# Power_Management.net
KiCad netlist of a schematic drawn in Altium Designer
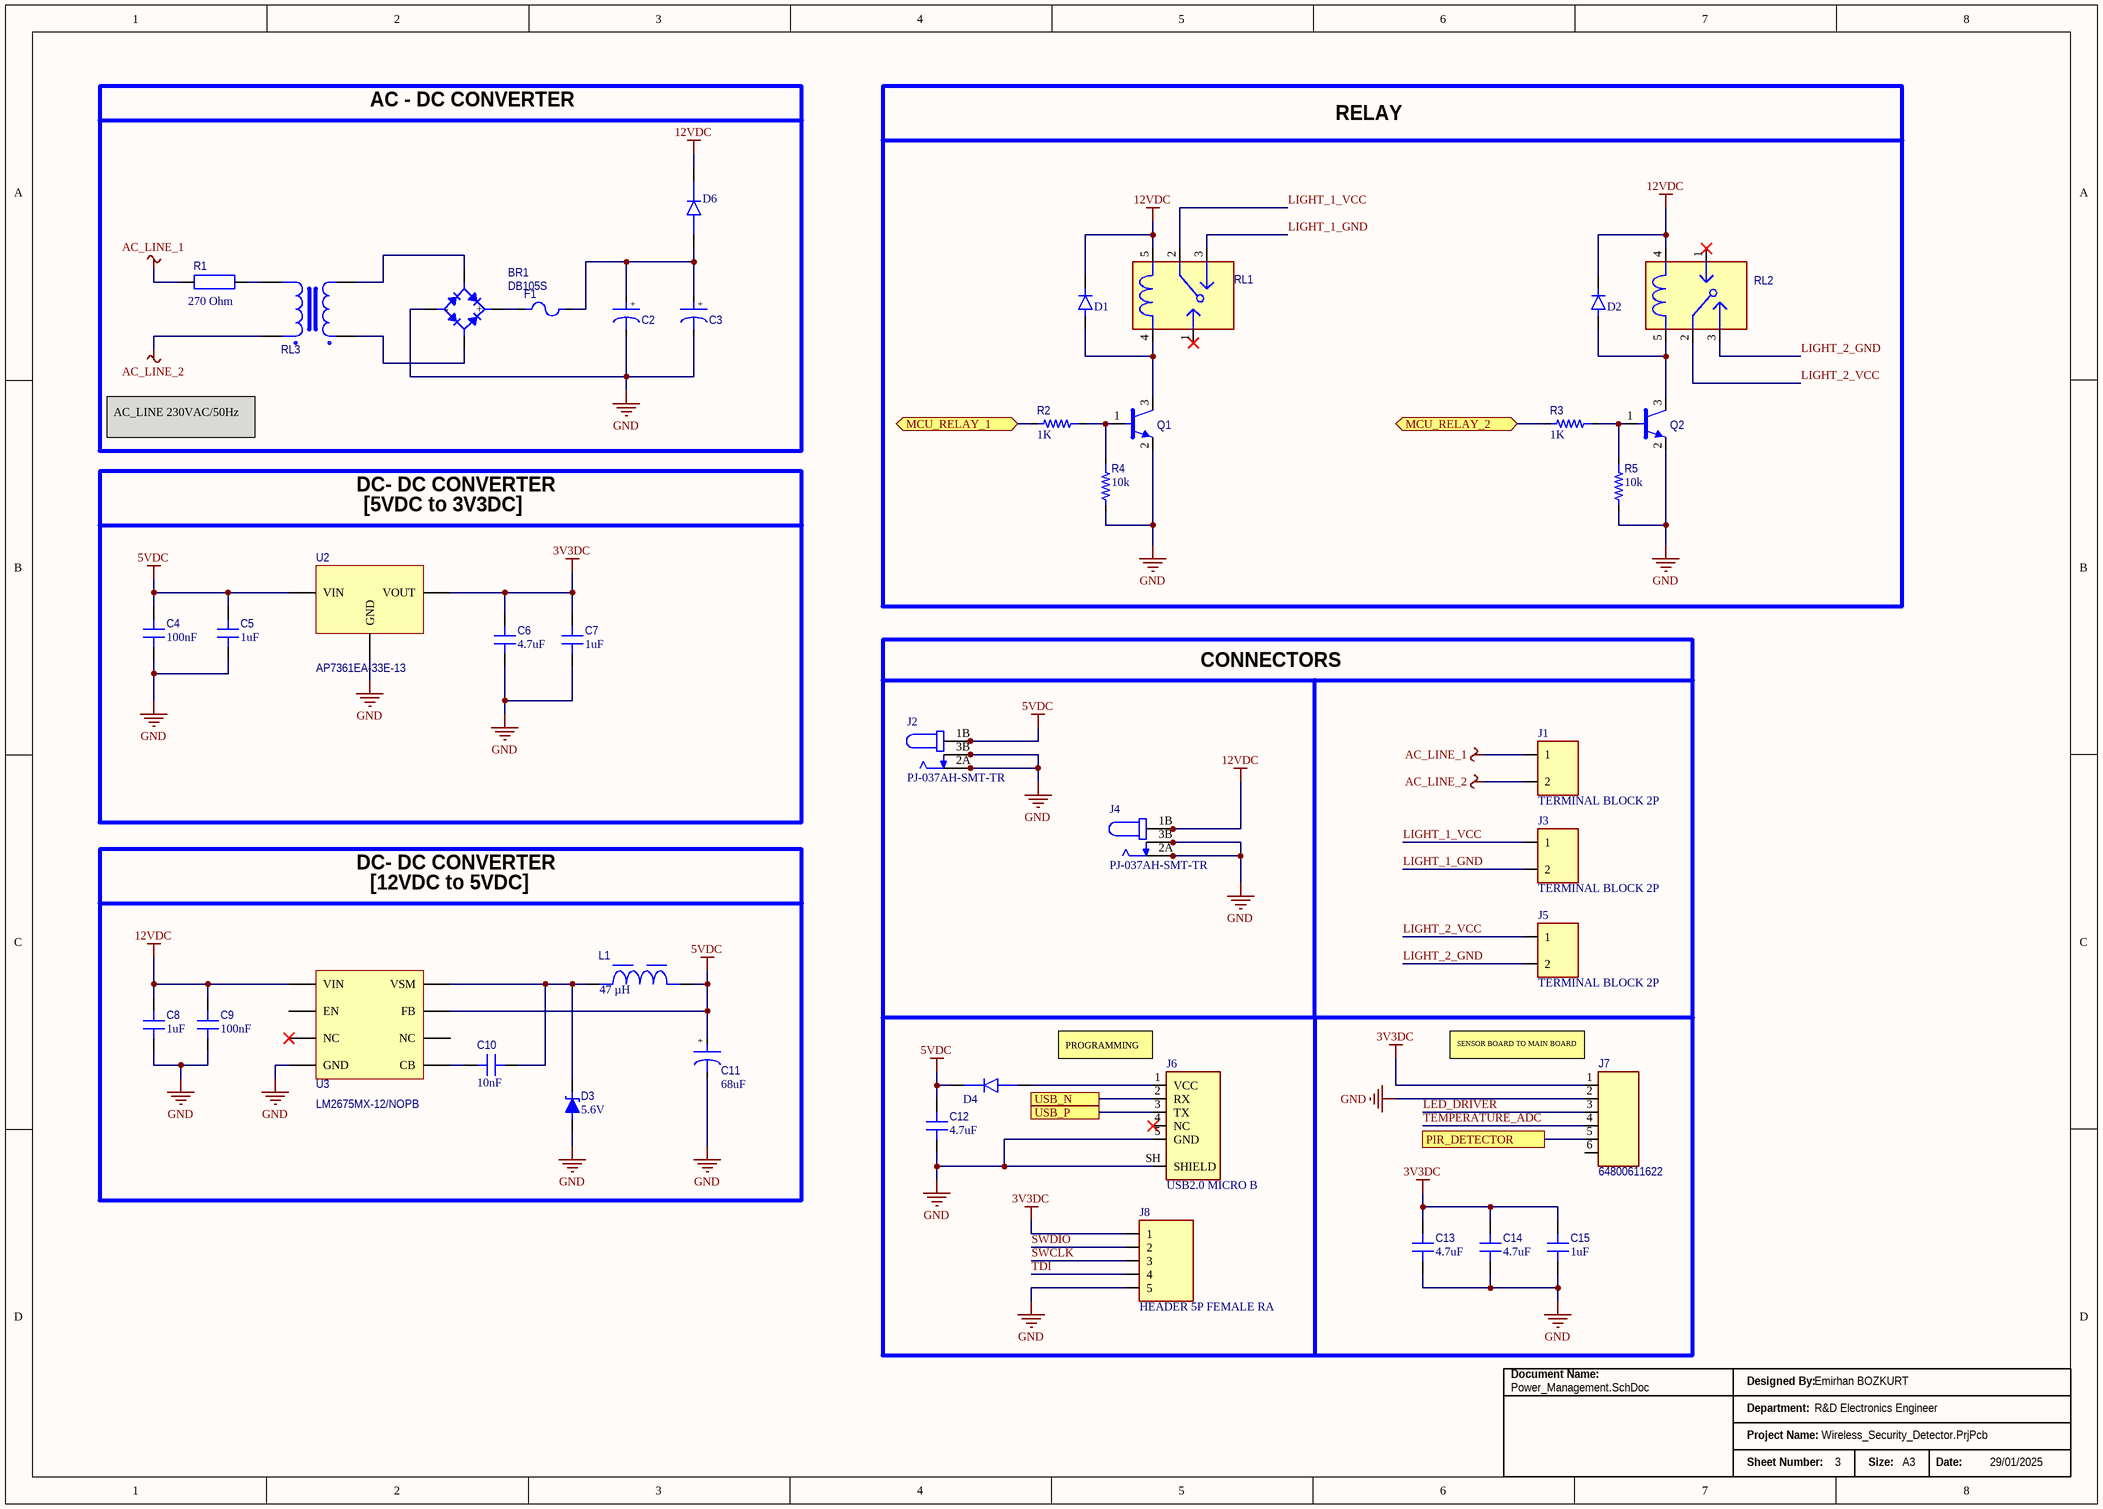
[diagram p0: Power_Management.SchDoc]

(export (version "E")
  (design (tool "Eeschema 10.0.6"))
  (components
    (comp (ref "BR1")
      (value "DB105S")
      (footprint "DB105S")
      (description "BRIDGE RECT 1PHASE 600V 1A DB-S")
      (fields (field (name "DESIGNED BY") "Emirhan Bozkurt"))
      (libsource (lib "Emirhan's") (part "DB105S"))
    )
    (comp (ref "C2")
      (value "ESH477M035AH3AA")
      (footprint "ESH477M035AH3AA")
      (description "CAP ALUM 470UF 20% 35V RADIAL TH")
      (fields (field (name "MANUFACTURER") "KEMET") (field (name "DESIGNED BY") "Emirhan Bozkurt"))
      (libsource (lib "Emirhan's") (part "CAP ALU 470uF TH"))
    )
    (comp (ref "C3")
      (value "ESH477M035AH3AA")
      (footprint "ESH477M035AH3AA")
      (description "CAP ALUM 470UF 20% 35V RADIAL TH")
      (fields (field (name "MANUFACTURER") "KEMET") (field (name "DESIGNED BY") "Emirhan Bozkurt"))
      (libsource (lib "Emirhan's") (part "CAP ALU 470uF TH"))
    )
    (comp (ref "C4")
      (value "100nF")
      (footprint "CAP_0805")
      (description "CAP CER 0.1uF 50V X7R 0805")
      (fields (field (name "Comment") "1276-1003-2-ND") (field (name "DESIGNED BY") "Emirhan Bozkurt"))
      (libsource (lib "Emirhan's") (part "CAP CER 100nF 0805"))
    )
    (comp (ref "C5")
      (value "1uF")
      (footprint "CAP_0805")
      (description "CAP CER 1uF 25V X5R 0805")
      (fields
        (field (name "MANUFACTURER") "Samsung Electro-Mechanics")
        (field (name "Comment") "CL21B105KBFNNNE")
        (field (name "DESIGNED BY") "Emirhan Bozkurt")
      )
      (libsource (lib "Emirhan's") (part "CAP CER 1uF 0805"))
    )
    (comp (ref "C6")
      (value "4.7uF")
      (footprint "CAP_0805")
      (description "CAP CER 4.7uF 25V X5R 0805")
      (fields
        (field (name "MANUFACTURER") "Samsung Electro-Mechanics")
        (field (name "Comment") "CL21A475KAQNNNE")
        (field (name "DESIGNED BY") "Emirhan Bozkurt")
      )
      (libsource (lib "Emirhan's") (part "CAP CER 4.7uF 0805"))
    )
    (comp (ref "C7")
      (value "1uF")
      (footprint "CAP_0805")
      (description "CAP CER 1uF 25V X5R 0805")
      (fields
        (field (name "MANUFACTURER") "Samsung Electro-Mechanics")
        (field (name "Comment") "CL21B105KBFNNNE")
        (field (name "DESIGNED BY") "Emirhan Bozkurt")
      )
      (libsource (lib "Emirhan's") (part "CAP CER 1uF 0805"))
    )
    (comp (ref "C8")
      (value "1uF")
      (footprint "CAP_0805")
      (description "CAP CER 1uF 25V X5R 0805")
      (fields
        (field (name "MANUFACTURER") "Samsung Electro-Mechanics")
        (field (name "Comment") "CL21B105KBFNNNE")
        (field (name "DESIGNED BY") "Emirhan Bozkurt")
      )
      (libsource (lib "Emirhan's") (part "CAP CER 1uF 0805"))
    )
    (comp (ref "C9")
      (value "100nF")
      (footprint "CAP_0805")
      (description "CAP CER 0.1uF 50V X7R 0805")
      (fields (field (name "Comment") "1276-1003-2-ND") (field (name "DESIGNED BY") "Emirhan Bozkurt"))
      (libsource (lib "Emirhan's") (part "CAP CER 100nF 0805"))
    )
    (comp (ref "C10")
      (value "10nF")
      (footprint "CAP_0603")
      (description "CAP CER 1000pF 50V X7R 0603")
      (fields
        (field (name "MANUFACTURER") "Samsung Electro-Mechanics")
        (field (name "Comment") "CL10B102KB8NNNC")
        (field (name "DESIGNED BY") "Emirhan Bozkurt")
      )
      (libsource (lib "Emirhan's") (part "CAP CER 10nF 0603"))
    )
    (comp (ref "C11")
      (value "68uF")
      (footprint "CAP_ALU_68uF")
      (description "CAP ALUM 68uF 20% 35V SMD")
      (fields
        (field (name "MANUFACTURER") "KEMET")
        (field (name "Comment") "EEV686M035A9HAA")
        (field (name "DESIGNED BY") "Emirhan Bozkurt")
      )
      (libsource (lib "Emirhan's") (part "CAP ALU 68uF SMD"))
    )
    (comp (ref "C12")
      (value "4.7uF")
      (footprint "CAP_0805")
      (description "CAP CER 4.7uF 25V X5R 0805")
      (fields
        (field (name "MANUFACTURER") "Samsung Electro-Mechanics")
        (field (name "Comment") "CL21A475KAQNNNE")
        (field (name "DESIGNED BY") "Emirhan Bozkurt")
      )
      (libsource (lib "Emirhan's") (part "CAP CER 4.7uF 0805"))
    )
    (comp (ref "C13")
      (value "4.7uF")
      (footprint "CAP_0805")
      (description "CAP CER 4.7uF 25V X5R 0805")
      (fields
        (field (name "MANUFACTURER") "Samsung Electro-Mechanics")
        (field (name "Comment") "CL21A475KAQNNNE")
        (field (name "DESIGNED BY") "Emirhan Bozkurt")
      )
      (libsource (lib "Emirhan's") (part "CAP CER 4.7uF 0805"))
    )
    (comp (ref "C14")
      (value "4.7uF")
      (footprint "CAP_0805")
      (description "CAP CER 4.7uF 25V X5R 0805")
      (fields
        (field (name "MANUFACTURER") "Samsung Electro-Mechanics")
        (field (name "Comment") "CL21A475KAQNNNE")
        (field (name "DESIGNED BY") "Emirhan Bozkurt")
      )
      (libsource (lib "Emirhan's") (part "CAP CER 4.7uF 0805"))
    )
    (comp (ref "C15")
      (value "1uF")
      (footprint "CAP_0805")
      (description "CAP CER 1uF 25V X5R 0805")
      (fields
        (field (name "MANUFACTURER") "Samsung Electro-Mechanics")
        (field (name "Comment") "CL21B105KBFNNNE")
        (field (name "DESIGNED BY") "Emirhan Bozkurt")
      )
      (libsource (lib "Emirhan's") (part "CAP CER 1uF 0805"))
    )
    (comp (ref "D1")
      (value "1N4148WS")
      (footprint "1N4148WS")
      (description "DIODE STANDARD 75V 150MA SOD323F")
      (fields
        (field (name "MANUFACTURER") "Diotec Semiconductor")
        (field (name "DESIGNED BY") "Emirhan Bozkurt")
      )
      (libsource (lib "Emirhan's") (part "1N4148WS"))
    )
    (comp (ref "D2")
      (value "1N4148WS")
      (footprint "1N4148WS")
      (description "DIODE STANDARD 75V 150MA SOD323F")
      (fields
        (field (name "MANUFACTURER") "Diotec Semiconductor")
        (field (name "DESIGNED BY") "Emirhan Bozkurt")
      )
      (libsource (lib "Emirhan's") (part "1N4148WS"))
    )
    (comp (ref "D3")
      (value "5.6V")
      (footprint "1SMB5919BT3G")
      (description "DIODE ZENER 5.6V 3W SMB")
      (fields (field (name "MANUFACTURER") "Onsemi") (field (name "Comment") "1SMB5919BT3G"))
      (libsource (lib "Emirhan's") (part "1SMB5919BT3G"))
    )
    (comp (ref "D4")
      (value "1N4148WS")
      (footprint "1N4148WS")
      (description "DIODE STANDARD 75V 150MA SOD323F")
      (fields
        (field (name "MANUFACTURER") "Diotec Semiconductor")
        (field (name "DESIGNED BY") "Emirhan Bozkurt")
      )
      (libsource (lib "") (part "1N4148WS_1"))
    )
    (comp (ref "D6")
      (value "1N4148WS")
      (footprint "1N4148WS")
      (description "DIODE STANDARD 75V 150MA SOD323F")
      (fields
        (field (name "MANUFACTURER") "Diotec Semiconductor")
        (field (name "DESIGNED BY") "Emirhan Bozkurt")
      )
      (libsource (lib "") (part "1N4148WS_1"))
    )
    (comp (ref "F1")
      (value "3413.0216.22")
      (footprint "FUSE 1A")
      (description "FUSE BRD MNT 1A 32VAC 63VDC 1206")
      (fields (field (name "DESIGNED BY") "Emirhan Bozkurt"))
      (libsource (lib "Emirhan's") (part "FUSE 1A"))
    )
    (comp (ref "J1")
      (value "TERMINAL BLOCK 2P")
      (footprint "TBP01R1-508")
      (fields (field (name "DESIGNED BY") "Emirhan Bozkurt"))
      (libsource (lib "Emirhan's") (part "TERMINAL BLOCK 2P"))
    )
    (comp (ref "J2")
      (value "PJ-037AH-SMT-TR")
      (footprint "PJ-037AH-SMT-TR")
      (description "CONN PWR JACK 2X5.5MM SOLDER")
      (fields (field (name "MANUFACTURER") "Same Sky") (field (name "DESIGNED BY") "Emirhan Bozkurt"))
      (libsource (lib "Emirhan's") (part "PJ-037AH-SMT-TR_1"))
    )
    (comp (ref "J3")
      (value "TERMINAL BLOCK 2P")
      (footprint "TBP01R1-508")
      (fields (field (name "DESIGNED BY") "Emirhan Bozkurt"))
      (libsource (lib "Emirhan's") (part "TERMINAL BLOCK 2P"))
    )
    (comp (ref "J4")
      (value "PJ-037AH-SMT-TR")
      (footprint "PJ-037AH-SMT-TR")
      (description "CONN PWR JACK 2X5.5MM SOLDER")
      (fields (field (name "MANUFACTURER") "Same Sky") (field (name "DESIGNED BY") "Emirhan Bozkurt"))
      (libsource (lib "Emirhan's") (part "PJ-037AH-SMT-TR_1"))
    )
    (comp (ref "J5")
      (value "TERMINAL BLOCK 2P")
      (footprint "TBP01R1-508")
      (fields (field (name "DESIGNED BY") "Emirhan Bozkurt"))
      (libsource (lib "Emirhan's") (part "TERMINAL BLOCK 2P"))
    )
    (comp (ref "J6")
      (value "USB2.0 MICRO B")
      (footprint "USB2.0 MICRO B")
      (description "CONN RCPT USB2.0 MICRO B SMD R/A")
      (fields (field (name "MANUFACTURER") "Amphenol ICC") (field (name "DESIGNED BY") "Emirhan Bozkurt"))
      (libsource (lib "Emirhan's") (part "USB2.0 MICRO B"))
    )
    (comp (ref "J7")
      (value "64800611622")
      (footprint "64800611622")
      (description "WR-WTB WIRE-TO-BOARD CONNECTORS")
      (fields (field (name "MANUFACTURER") "WE") (field (name "DESIGNED BY") "Emirhan Bozkurt"))
      (libsource (lib "Emirhan's") (part "64800611622-CONN-6P"))
    )
    (comp (ref "J8")
      (value "HEADER 5P FEMALE RA")
      (footprint "HDR_5_POS_CONN_RA")
      (description "CONN RCPT 5POS 0.1 GOLD SMD R/A")
      (fields (field (name "MANUFACTURER") "Samtec"))
      (libsource (lib "Emirhan's") (part "HEADER 5P FEMALE RA"))
    )
    (comp (ref "L1")
      (value "47 µH")
      (footprint "INT_47uL")
      (description "FIXED IND 47UH 390MA 2.3 OHM SMD")
      (fields
        (field (name "SUPPLY  PART NUMBER") "732-6947-2-ND")
        (field (name "MANUFACTURER") "Würth")
        (field (name "DESIGNED BY") "Emirhan Bozkurt")
      )
      (libsource (lib "Emirhan's") (part "INT 47uH"))
    )
    (comp (ref "Q1")
      (value "MMBT3904-7-F")
      (footprint "SOT-23F")
      (description "TRANS NPN 40V 0.2A SOT-23-3")
      (libsource (lib "Emirhan's") (part "MMBT3904-7-F"))
    )
    (comp (ref "Q2")
      (value "MMBT3904-7-F")
      (footprint "SOT-23F")
      (description "TRANS NPN 40V 0.2A SOT-23-3")
      (libsource (lib "Emirhan's") (part "MMBT3904-7-F"))
    )
    (comp (ref "R1")
      (value "270 Ohm")
      (footprint "RES_AXIAL_W")
      (description "RES WIREWOUND 270 Ohm")
      (fields (field (name "Comment") "5WD27"))
      (libsource (lib "Emirhan_Bozkurt's") (part "5WD27"))
    )
    (comp (ref "R2")
      (value "1K")
      (footprint "RES_0603")
      (description "RES 1K 1% 1/10W 0603")
      (fields
        (field (name "SUPPIER PART NUMBER") "311-1.00KHRCT-ND")
        (field (name "MANUFACTURER") "YAGEO")
        (field (name "DESIGNED BY") "Emirhan Bozkurt")
      )
      (libsource (lib "Emirhan's") (part "RES 1K 0603"))
    )
    (comp (ref "R3")
      (value "1K")
      (footprint "RES_0603")
      (description "RES 1K 1% 1/10W 0603")
      (fields
        (field (name "SUPPIER PART NUMBER") "311-1.00KHRCT-ND")
        (field (name "MANUFACTURER") "YAGEO")
        (field (name "DESIGNED BY") "Emirhan Bozkurt")
      )
      (libsource (lib "Emirhan's") (part "RES 1K 0603"))
    )
    (comp (ref "R4")
      (value "10k")
      (footprint "RES_0603")
      (description "RES 10K OHM 1% 1/10W 0603")
      (fields
        (field (name "SUPPIER PART NUMBER") "311-10.0KHRTR-ND")
        (field (name "MANUFACTURER") "YAGEO")
        (field (name "DESIGNED BY") "Emirhan Bozkurt")
      )
      (libsource (lib "Emirhan's") (part "RES 10K 0603"))
    )
    (comp (ref "R5")
      (value "10k")
      (footprint "RES_0603")
      (description "RES 10K OHM 1% 1/10W 0603")
      (fields
        (field (name "SUPPIER PART NUMBER") "311-10.0KHRTR-ND")
        (field (name "MANUFACTURER") "YAGEO")
        (field (name "DESIGNED BY") "Emirhan Bozkurt")
      )
      (libsource (lib "Emirhan's") (part "RES 10K 0603"))
    )
    (comp (ref "RL1")
      (value "ALQ112")
      (footprint "ALQ112")
      (description "RELAY GEN PURPOSE SPDT 10A 12V")
      (fields (field (name "DESIGNED BY") "Emirhan Bozkurt"))
      (libsource (lib "Emirhan's") (part "ALQ112"))
    )
    (comp (ref "RL2")
      (value "ALQ112")
      (footprint "ALQ112")
      (description "RELAY GEN PURPOSE SPDT 10A 12V")
      (fields (field (name "DESIGNED BY") "Emirhan Bozkurt"))
      (libsource (lib "") (part "ALQ112_1"))
    )
    (comp (ref "RL3")
      (value "BV302S12010")
      (footprint "BV302S12010")
      (description "230V - 12V PWR XFMR 1VA TH")
      (fields (field (name "DESIGNED BY") "Emirhan Bozkurt"))
      (libsource (lib "Emirhan_Bozkurt's") (part "BV302S12010"))
    )
    (comp (ref "U2")
      (value "AP7361EA-33E-13")
      (footprint "AP7361EA-33E-13")
      (description "LDO CMOS HICURR SOT223 T&R 2.5K")
      (fields (field (name "DESIGNED BY") "Emirhan Bozkurt"))
      (libsource (lib "Emirhan's") (part "AP7361EA-33E-13"))
    )
    (comp (ref "U3")
      (value "LM2675MX-12/NOPB")
      (footprint "LM2675MX-12/NOPB")
      (description "IC REG BUCK 12V 1A SOIC-8")
      (fields (field (name "DESIGNED BY") "Emirhan Bozkurt"))
      (libsource (lib "Emirhan's") (part "LM2675MX-12/NOPB"))
    )
  )
  (nets
    (net (code "1") (name "/LED_DRIVER") (class "Default") (node (ref "J7") (pin "3") (pintype "passive")))
    (net (code "2") (name "/LIGHT_1_GND") (class "Default")
      (node (ref "J3") (pin "2") (pinfunction "2_2") (pintype "passive"))
      (node (ref "RL1") (pin "3") (pinfunction "NO_3") (pintype "passive"))
    )
    (net (code "3") (name "/LIGHT_1_VCC") (class "Default")
      (node (ref "J3") (pin "1") (pinfunction "1_1") (pintype "passive"))
      (node (ref "RL1") (pin "2") (pinfunction "NC_2") (pintype "passive"))
    )
    (net (code "4") (name "/LIGHT_2_GND") (class "Default")
      (node (ref "J5") (pin "2") (pinfunction "2_2") (pintype "passive"))
      (node (ref "RL2") (pin "3") (pinfunction "NO_3") (pintype "passive"))
    )
    (net (code "5") (name "/LIGHT_2_VCC") (class "Default")
      (node (ref "J5") (pin "1") (pinfunction "1_1") (pintype "passive"))
      (node (ref "RL2") (pin "2") (pinfunction "NC_2") (pintype "passive"))
    )
    (net (code "6") (name "/MCU_RELAY_1") (class "Default")
      (node (ref "R2") (pin "1") (pinfunction "1_1") (pintype "passive"))
    )
    (net (code "7") (name "/MCU_RELAY_2") (class "Default")
      (node (ref "R3") (pin "1") (pinfunction "1_1") (pintype "passive"))
    )
    (net (code "8") (name "/PIR_DETECTOR") (class "Default") (node (ref "J7") (pin "5") (pintype "passive")))
    (net (code "9") (name "/SWCLK") (class "Default")
      (node (ref "J8") (pin "3") (pinfunction "3_3") (pintype "passive"))
    )
    (net (code "10") (name "/SWDIO") (class "Default")
      (node (ref "J8") (pin "2") (pinfunction "2_2") (pintype "passive"))
    )
    (net (code "11") (name "/TDI") (class "Default")
      (node (ref "J8") (pin "4") (pinfunction "4_4") (pintype "passive"))
    )
    (net (code "12") (name "/TEMPERATURE_ADC") (class "Default")
      (node (ref "J7") (pin "4") (pintype "passive"))
    )
    (net (code "13") (name "/USB_N") (class "Default")
      (node (ref "J6") (pin "2") (pinfunction "RX_2") (pintype "passive"))
    )
    (net (code "14") (name "/USB_P") (class "Default")
      (node (ref "J6") (pin "3") (pinfunction "TX_3") (pintype "passive"))
    )
    (net (code "15") (name "3V3DC") (class "Default")
      (node (ref "C13") (pin "2") (pinfunction "2_2") (pintype "passive"))
      (node (ref "C14") (pin "2") (pinfunction "2_2") (pintype "passive"))
      (node (ref "C15") (pin "2") (pinfunction "2_2") (pintype "passive"))
      (node (ref "C6") (pin "2") (pinfunction "2_2") (pintype "passive"))
      (node (ref "C7") (pin "2") (pinfunction "2_2") (pintype "passive"))
      (node (ref "J7") (pin "1") (pintype "passive"))
      (node (ref "J8") (pin "1") (pinfunction "1_1") (pintype "passive"))
      (node (ref "U2") (pin "3") (pinfunction "VOUT_3") (pintype "passive"))
    )
    (net (code "16") (name "5VDC") (class "Default")
      (node (ref "C11") (pin "1") (pinfunction "A_1") (pintype "passive"))
      (node (ref "C12") (pin "2") (pinfunction "2_2") (pintype "passive"))
      (node (ref "C4") (pin "2") (pinfunction "2_2") (pintype "passive"))
      (node (ref "C5") (pin "2") (pinfunction "2_2") (pintype "passive"))
      (node (ref "D4") (pin "C") (pinfunction "C_C") (pintype "passive"))
      (node (ref "J2") (pin "1A") (pinfunction "1_1A") (pintype "passive"))
      (node (ref "J2") (pin "1B") (pinfunction "1_1B") (pintype "passive"))
      (node (ref "L1") (pin "2") (pinfunction "2_2") (pintype "passive"))
      (node (ref "U2") (pin "1") (pinfunction "VIN_1") (pintype "passive"))
      (node (ref "U3") (pin "4") (pinfunction "FB_4") (pintype "passive"))
    )
    (net (code "17") (name "12VDC") (class "Default")
      (node (ref "C8") (pin "2") (pinfunction "2_2") (pintype "passive"))
      (node (ref "C9") (pin "2") (pinfunction "2_2") (pintype "passive"))
      (node (ref "D1") (pin "C") (pinfunction "C_C") (pintype "passive"))
      (node (ref "D2") (pin "C") (pinfunction "C_C") (pintype "passive"))
      (node (ref "D6") (pin "C") (pinfunction "C_C") (pintype "passive"))
      (node (ref "J4") (pin "1A") (pinfunction "1_1A") (pintype "passive"))
      (node (ref "J4") (pin "1B") (pinfunction "1_1B") (pintype "passive"))
      (node (ref "RL1") (pin "5") (pinfunction "5_5") (pintype "passive"))
      (node (ref "RL2") (pin "4") (pinfunction "4_4") (pintype "passive"))
      (node (ref "U3") (pin "7") (pinfunction "VIN_7") (pintype "passive"))
    )
    (net (code "18") (name "AC_LINE_1") (class "Default")
      (node (ref "J1") (pin "1") (pinfunction "1_1") (pintype "passive"))
      (node (ref "R1") (pin "1") (pinfunction "1_1") (pintype "passive"))
    )
    (net (code "19") (name "AC_LINE_2") (class "Default")
      (node (ref "J1") (pin "2") (pinfunction "2_2") (pintype "passive"))
      (node (ref "RL3") (pin "1") (pinfunction "1_1") (pintype "passive"))
    )
    (net (code "20") (name "GND") (class "Default")
      (node (ref "BR1") (pin "4") (pinfunction "-_4") (pintype "passive"))
      (node (ref "C11") (pin "2") (pinfunction "K_2") (pintype "passive"))
      (node (ref "C12") (pin "1") (pinfunction "1_1") (pintype "passive"))
      (node (ref "C13") (pin "1") (pinfunction "1_1") (pintype "passive"))
      (node (ref "C14") (pin "1") (pinfunction "1_1") (pintype "passive"))
      (node (ref "C15") (pin "1") (pinfunction "1_1") (pintype "passive"))
      (node (ref "C2") (pin "2") (pinfunction "K_2") (pintype "passive"))
      (node (ref "C3") (pin "2") (pinfunction "K_2") (pintype "passive"))
      (node (ref "C4") (pin "1") (pinfunction "1_1") (pintype "passive"))
      (node (ref "C5") (pin "1") (pinfunction "1_1") (pintype "passive"))
      (node (ref "C6") (pin "1") (pinfunction "1_1") (pintype "passive"))
      (node (ref "C7") (pin "1") (pinfunction "1_1") (pintype "passive"))
      (node (ref "C8") (pin "1") (pinfunction "1_1") (pintype "passive"))
      (node (ref "C9") (pin "1") (pinfunction "1_1") (pintype "passive"))
      (node (ref "D3") (pin "1") (pinfunction "1_1") (pintype "passive"))
      (node (ref "J2") (pin "2A") (pinfunction "2_2A") (pintype "passive"))
      (node (ref "J2") (pin "2B") (pinfunction "2_2B") (pintype "passive"))
      (node (ref "J2") (pin "3A") (pinfunction "3_3A") (pintype "passive"))
      (node (ref "J2") (pin "3B") (pinfunction "3_3B") (pintype "passive"))
      (node (ref "J4") (pin "2A") (pinfunction "2_2A") (pintype "passive"))
      (node (ref "J4") (pin "2B") (pinfunction "2_2B") (pintype "passive"))
      (node (ref "J4") (pin "3A") (pinfunction "3_3A") (pintype "passive"))
      (node (ref "J4") (pin "3B") (pinfunction "3_3B") (pintype "passive"))
      (node (ref "J6") (pin "5") (pinfunction "GND_5") (pintype "passive"))
      (node (ref "J6") (pin "SH") (pinfunction "SHIELD_SH") (pintype "passive"))
      (node (ref "J7") (pin "2") (pintype "passive"))
      (node (ref "J8") (pin "5") (pinfunction "5_5") (pintype "passive"))
      (node (ref "Q1") (pin "2") (pinfunction "E_2") (pintype "passive"))
      (node (ref "Q2") (pin "2") (pinfunction "E_2") (pintype "passive"))
      (node (ref "R4") (pin "1") (pinfunction "1_1") (pintype "passive"))
      (node (ref "R5") (pin "1") (pinfunction "1_1") (pintype "passive"))
      (node (ref "U2") (pin "2") (pinfunction "GND_2") (pintype "passive"))
      (node (ref "U3") (pin "6") (pinfunction "GND_6") (pintype "passive"))
    )
    (net (code "21") (name "Net-(BR1-+)") (class "Default")
      (node (ref "BR1") (pin "3") (pinfunction "+_3") (pintype "passive"))
      (node (ref "F1") (pin "1") (pinfunction "1_1") (pintype "passive"))
    )
    (net (code "22") (name "Net-(BR1-Pad1)") (class "Default")
      (node (ref "BR1") (pin "1") (pinfunction "1_1") (pintype "passive"))
      (node (ref "RL3") (pin "9") (pinfunction "9_9") (pintype "passive"))
    )
    (net (code "23") (name "Net-(BR1-Pad2)") (class "Default")
      (node (ref "BR1") (pin "2") (pinfunction "2_2") (pintype "passive"))
      (node (ref "RL3") (pin "7") (pinfunction "7_7") (pintype "passive"))
    )
    (net (code "24") (name "Net-(C2-A)") (class "Default")
      (node (ref "C2") (pin "1") (pinfunction "A_1") (pintype "passive"))
      (node (ref "C3") (pin "1") (pinfunction "A_1") (pintype "passive"))
      (node (ref "D6") (pin "A") (pinfunction "A_A") (pintype "passive"))
      (node (ref "F1") (pin "2") (pinfunction "2_2") (pintype "passive"))
    )
    (net (code "25") (name "Net-(J6-VCC)") (class "Default")
      (node (ref "D4") (pin "A") (pinfunction "A_A") (pintype "passive"))
      (node (ref "J6") (pin "1") (pinfunction "VCC_1") (pintype "passive"))
    )
    (net (code "26") (name "Net-(Q1-B)") (class "Default")
      (node (ref "Q1") (pin "1") (pinfunction "B_1") (pintype "passive"))
      (node (ref "R2") (pin "2") (pinfunction "2_2") (pintype "passive"))
      (node (ref "R4") (pin "2") (pinfunction "2_2") (pintype "passive"))
    )
    (net (code "27") (name "Net-(Q1-C)") (class "Default")
      (node (ref "D1") (pin "A") (pinfunction "A_A") (pintype "passive"))
      (node (ref "Q1") (pin "3") (pinfunction "C_3") (pintype "passive"))
      (node (ref "RL1") (pin "4") (pinfunction "4_4") (pintype "passive"))
    )
    (net (code "28") (name "Net-(Q2-B)") (class "Default")
      (node (ref "Q2") (pin "1") (pinfunction "B_1") (pintype "passive"))
      (node (ref "R3") (pin "2") (pinfunction "2_2") (pintype "passive"))
      (node (ref "R5") (pin "2") (pinfunction "2_2") (pintype "passive"))
    )
    (net (code "29") (name "Net-(Q2-C)") (class "Default")
      (node (ref "D2") (pin "A") (pinfunction "A_A") (pintype "passive"))
      (node (ref "Q2") (pin "3") (pinfunction "C_3") (pintype "passive"))
      (node (ref "RL2") (pin "5") (pinfunction "5_5") (pintype "passive"))
    )
    (net (code "30") (name "Net-(R1-Pad2)") (class "Default")
      (node (ref "R1") (pin "2") (pinfunction "2_2") (pintype "passive"))
      (node (ref "RL3") (pin "5") (pinfunction "5_5") (pintype "passive"))
    )
    (net (code "31") (name "Net-(U3-CB)") (class "Default")
      (node (ref "C10") (pin "1") (pinfunction "1_1") (pintype "passive"))
      (node (ref "U3") (pin "1") (pinfunction "CB_1") (pintype "passive"))
    )
    (net (code "32") (name "Net-(U3-VSM)") (class "Default")
      (node (ref "C10") (pin "2") (pinfunction "2_2") (pintype "passive"))
      (node (ref "D3") (pin "2") (pinfunction "2_2") (pintype "passive"))
      (node (ref "L1") (pin "1") (pinfunction "1_1") (pintype "passive"))
      (node (ref "U3") (pin "8") (pinfunction "VSM_8") (pintype "passive"))
    )
    (net (code "33") (name "unconnected-(J6-NC-Pad4)") (class "Default")
      (node (ref "J6") (pin "4") (pinfunction "NC_4") (pintype "passive+no_connect"))
    )
    (net (code "34") (name "unconnected-(J7-Pad6)") (class "Default")
      (node (ref "J7") (pin "6") (pintype "passive"))
    )
    (net (code "35") (name "unconnected-(RL1-COM-Pad1)") (class "Default")
      (node (ref "RL1") (pin "1") (pinfunction "COM_1") (pintype "passive+no_connect"))
    )
    (net (code "36") (name "unconnected-(RL2-COM-Pad1)") (class "Default")
      (node (ref "RL2") (pin "1") (pinfunction "COM_1") (pintype "passive+no_connect"))
    )
    (net (code "37") (name "unconnected-(U3-EN-Pad5)") (class "Default")
      (node (ref "U3") (pin "5") (pinfunction "EN_5") (pintype "passive"))
    )
    (net (code "38") (name "unconnected-(U3-NC-Pad2)") (class "Default")
      (node (ref "U3") (pin "2") (pinfunction "NC_2") (pintype "passive+no_connect"))
    )
    (net (code "39") (name "unconnected-(U3-NC-Pad3)") (class "Default")
      (node (ref "U3") (pin "3") (pinfunction "NC_3") (pintype "passive"))
    )
  )
)
